# FMC_connector.net
KiCad netlist of a schematic drawn in Altium Designer
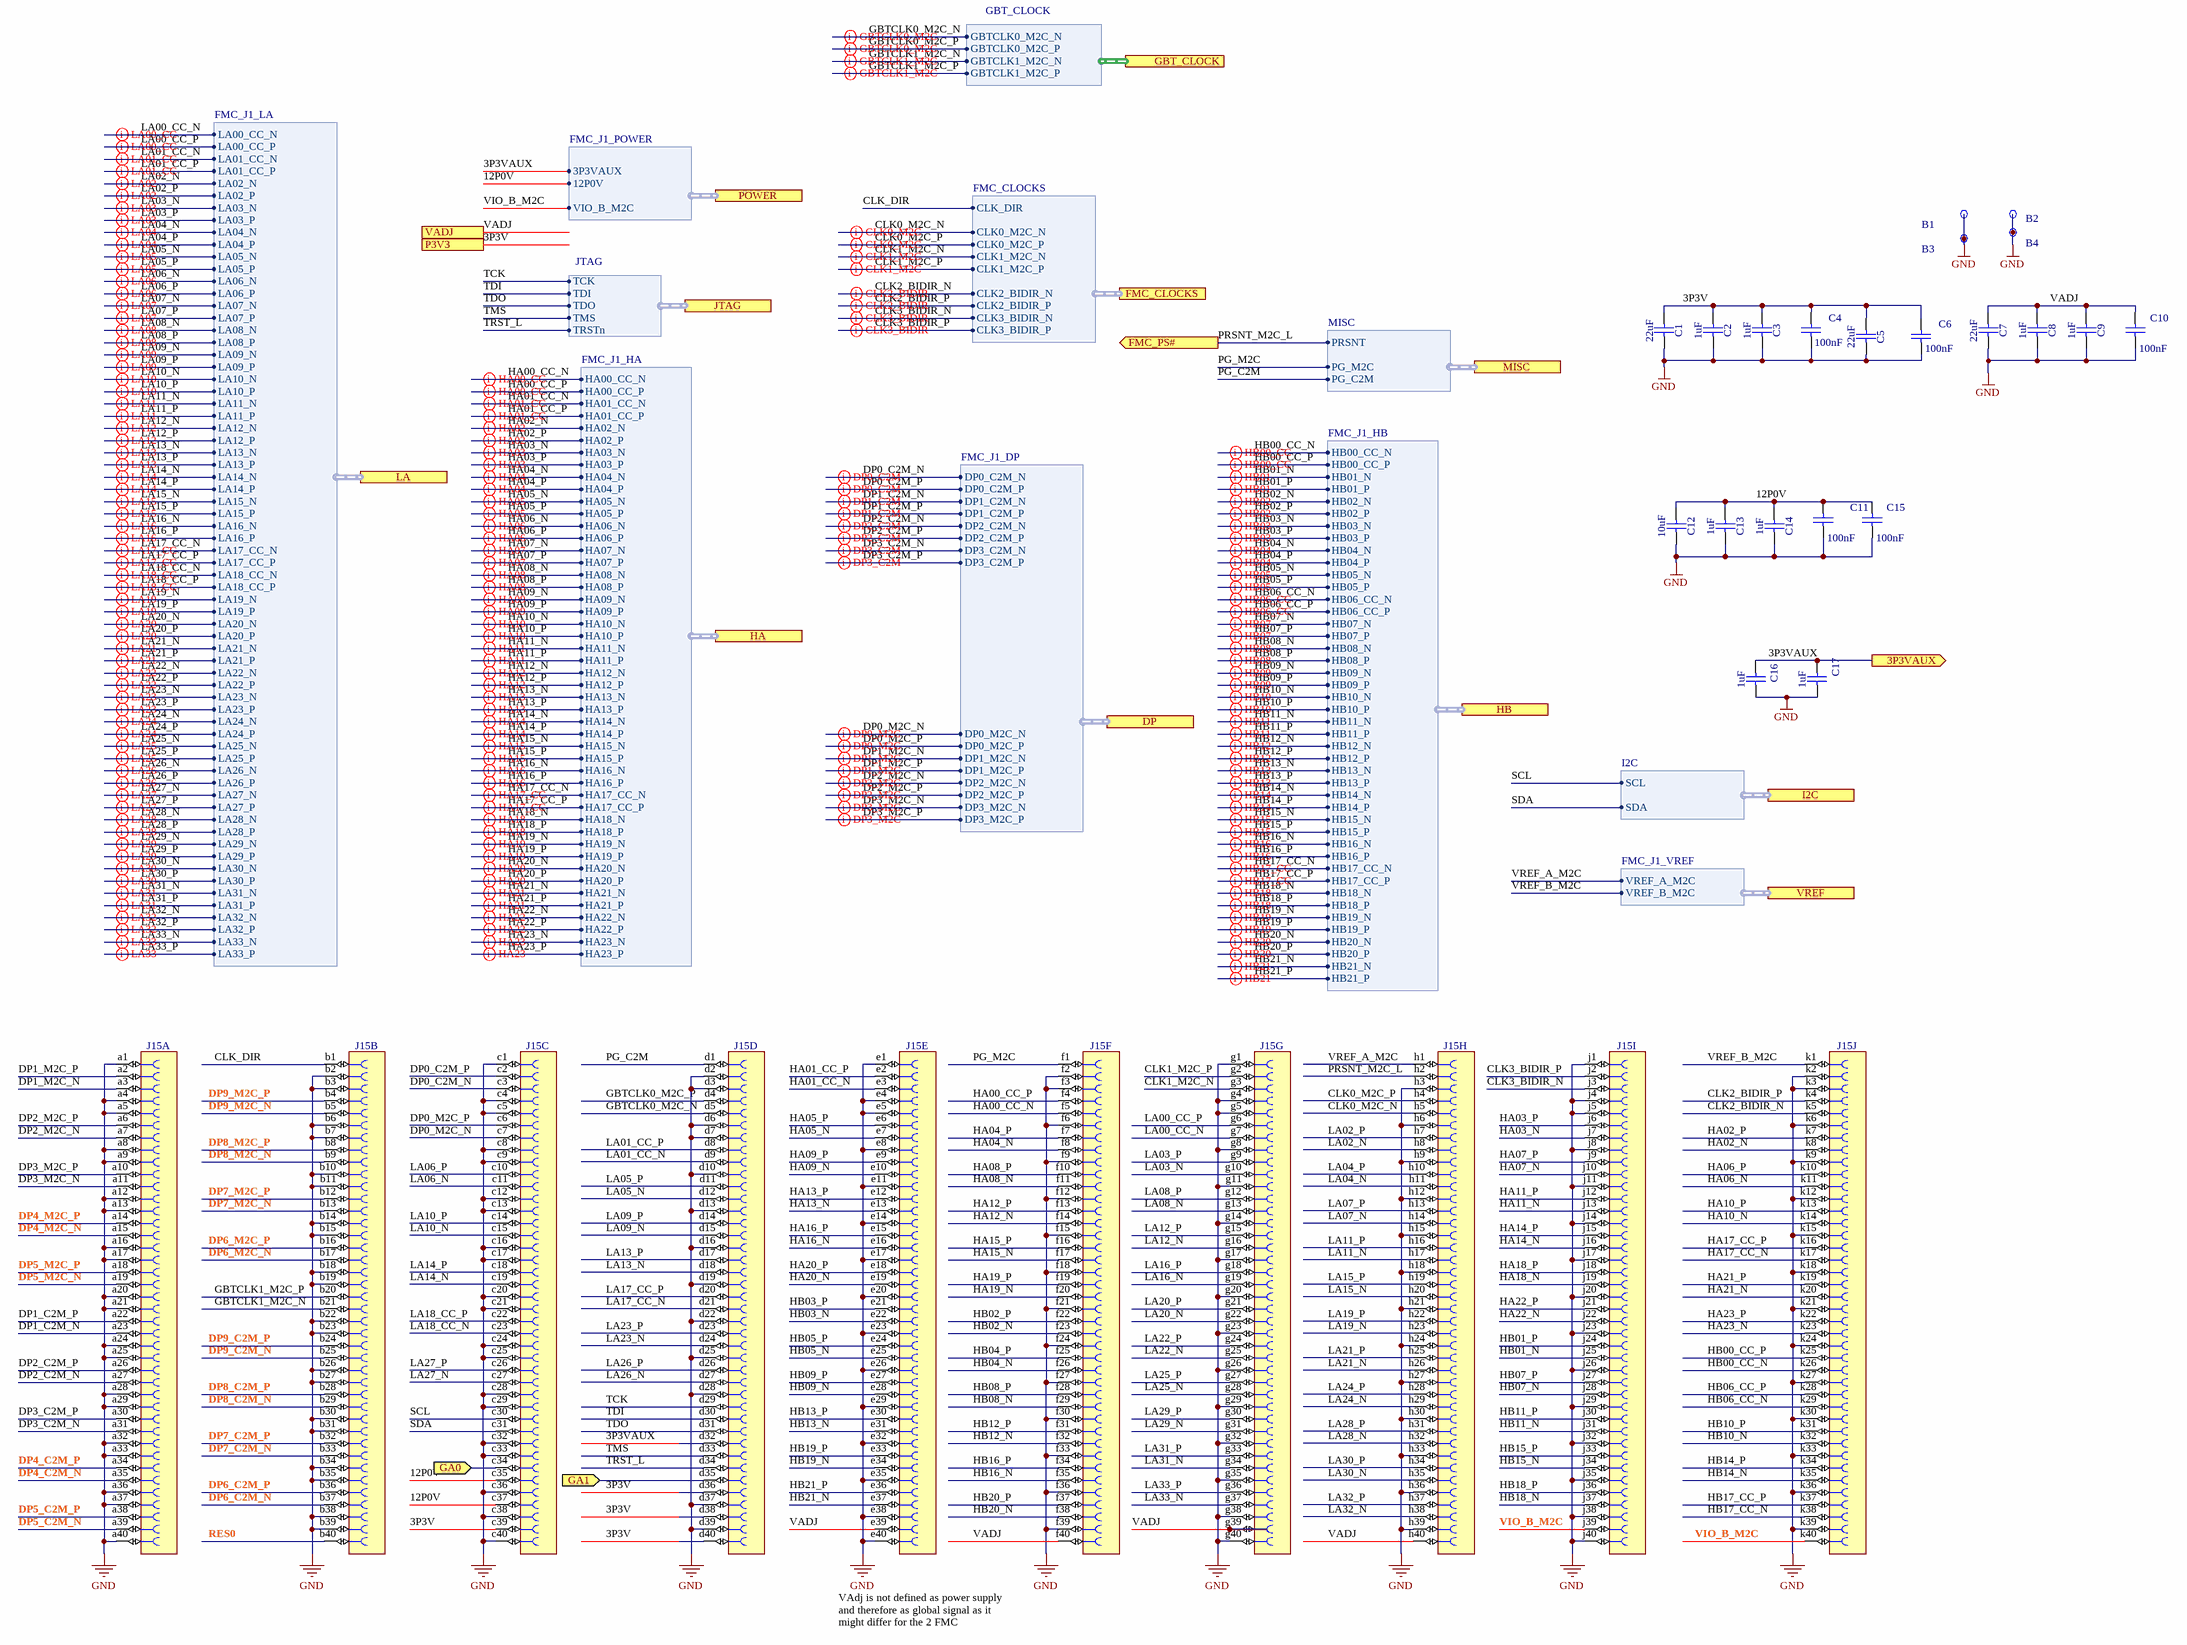
[diagram p0: FMC_connector.SchDoc]

(export (version "E")
  (design (tool "Eeschema 10.0.6"))
  (components
    (comp (ref "B1")
      (value "Plated Hole")
      (footprint "MTG270_500")
      (description "Single Terminal Socket")
      (fields (field (name "PART NUMBER") "PLATED_HOLE2.7_PAD5.0") (field (name "AUTHOR") "CERN DEM JMW"))
      (libsource (lib "Eletro-mechanical") (part "Single Terminal Socket"))
    )
    (comp (ref "B2")
      (value "Plated Hole")
      (footprint "MTG270_500")
      (description "Single Terminal Socket")
      (fields (field (name "PART NUMBER") "PLATED_HOLE2.7_PAD5.0") (field (name "AUTHOR") "CERN DEM JMW"))
      (libsource (lib "Eletro-mechanical") (part "Single Terminal Socket"))
    )
    (comp (ref "B3")
      (value "Plated Hole")
      (footprint "MTG270_500")
      (description "Single Terminal Socket")
      (fields (field (name "PART NUMBER") "PLATED_HOLE2.7_PAD5.0") (field (name "AUTHOR") "CERN DEM JMW"))
      (libsource (lib "Eletro-mechanical") (part "Single Terminal Socket"))
    )
    (comp (ref "B4")
      (value "Plated Hole")
      (footprint "MTG270_500")
      (description "Single Terminal Socket")
      (fields (field (name "PART NUMBER") "PLATED_HOLE2.7_PAD5.0") (field (name "AUTHOR") "CERN DEM JMW"))
      (libsource (lib "Eletro-mechanical") (part "Single Terminal Socket"))
    )
    (comp (ref "C1")
      (value "22uF")
      (footprint "CAPC3216X180N")
      (description "Non-polarised capacitor")
      (fields
        (field (name "PART NUMBER") "CC1206_22UF_10V_10%_X7R")
        (field (name "VOLTAGE") "10V")
        (field (name "AUTHOR") "CERN DEM JLC")
      )
      (libsource (lib "Capacitors") (part "Capacitor - non polarized"))
    )
    (comp (ref "C2")
      (value "1uF")
      (footprint "CAPC1608X87N")
      (description "Non-polarised capacitor")
      (fields
        (field (name "PART NUMBER") "CC0603_1UF_16V_10%_X7R")
        (field (name "VOLTAGE") "16V")
        (field (name "AUTHOR") "CERN DEM JLC")
      )
      (libsource (lib "Capacitors") (part "Capacitor - non polarized"))
    )
    (comp (ref "C3")
      (value "1uF")
      (footprint "CAPC1608X87N")
      (description "Non-polarised capacitor")
      (fields
        (field (name "PART NUMBER") "CC0603_1UF_16V_10%_X7R")
        (field (name "VOLTAGE") "16V")
        (field (name "AUTHOR") "CERN DEM JLC")
      )
      (libsource (lib "Capacitors") (part "Capacitor - non polarized"))
    )
    (comp (ref "C4")
      (value "100nF")
      (footprint "CAPC0603X33N")
      (description "Non-polarised capacitor")
      (fields
        (field (name "PART NUMBER") "CC0201_100NF_6.3V_10%_X5R")
        (field (name "VOLTAGE") "6.3V")
        (field (name "AUTHOR") "CERN DEM JLC")
      )
      (libsource (lib "Capacitors") (part "Capacitor - non polarized"))
    )
    (comp (ref "C5")
      (value "22uF")
      (footprint "CAPC3216X180N")
      (description "Non-polarised capacitor")
      (fields
        (field (name "PART NUMBER") "CC1206_22UF_10V_10%_X7R")
        (field (name "VOLTAGE") "10V")
        (field (name "AUTHOR") "CERN DEM JLC")
      )
      (libsource (lib "Capacitors") (part "Capacitor - non polarized"))
    )
    (comp (ref "C6")
      (value "100nF")
      (footprint "CAPC0603X33N")
      (description "Non-polarised capacitor")
      (fields
        (field (name "PART NUMBER") "CC0201_100NF_6.3V_10%_X5R")
        (field (name "VOLTAGE") "6.3V")
        (field (name "AUTHOR") "CERN DEM JLC")
      )
      (libsource (lib "Capacitors") (part "Capacitor - non polarized"))
    )
    (comp (ref "C7")
      (value "22uF")
      (footprint "CAPC3216X180N")
      (description "Non-polarised capacitor")
      (fields
        (field (name "PART NUMBER") "CC1206_22UF_10V_10%_X7R")
        (field (name "VOLTAGE") "10V")
        (field (name "AUTHOR") "CERN DEM JLC")
      )
      (libsource (lib "Capacitors") (part "Capacitor - non polarized"))
    )
    (comp (ref "C8")
      (value "1uF")
      (footprint "CAPC1608X87N")
      (description "Non-polarised capacitor")
      (fields
        (field (name "PART NUMBER") "CC0603_1UF_16V_10%_X7R")
        (field (name "VOLTAGE") "16V")
        (field (name "AUTHOR") "CERN DEM JLC")
      )
      (libsource (lib "Capacitors") (part "Capacitor - non polarized"))
    )
    (comp (ref "C9")
      (value "1uF")
      (footprint "CAPC1608X87N")
      (description "Non-polarised capacitor")
      (fields
        (field (name "PART NUMBER") "CC0603_1UF_16V_10%_X7R")
        (field (name "VOLTAGE") "16V")
        (field (name "AUTHOR") "CERN DEM JLC")
      )
      (libsource (lib "Capacitors") (part "Capacitor - non polarized"))
    )
    (comp (ref "C10")
      (value "100nF")
      (footprint "CAPC0603X33N")
      (description "Non-polarised capacitor")
      (fields
        (field (name "PART NUMBER") "CC0201_100NF_6.3V_10%_X5R")
        (field (name "VOLTAGE") "6.3V")
        (field (name "AUTHOR") "CERN DEM JLC")
      )
      (libsource (lib "Capacitors") (part "Capacitor - non polarized"))
    )
    (comp (ref "C11")
      (value "100nF")
      (footprint "CAPC0603X33N")
      (description "Non-polarised capacitor")
      (fields
        (field (name "PART NUMBER") "CC0201_100NF_6.3V_10%_X5R")
        (field (name "VOLTAGE") "6.3V")
        (field (name "AUTHOR") "CERN DEM JLC")
      )
      (libsource (lib "Capacitors") (part "Capacitor - non polarized"))
    )
    (comp (ref "C12")
      (value "10uF")
      (footprint "CAPC2012X135N")
      (description "Non-polarised capacitor")
      (fields
        (field (name "PART NUMBER") "CC0805_10UF_16V_10%_X5R")
        (field (name "VOLTAGE") "16V")
        (field (name "AUTHOR") "CERN DEM JLC")
      )
      (libsource (lib "Capacitors") (part "Capacitor - non polarized"))
    )
    (comp (ref "C13")
      (value "1uF")
      (footprint "CAPC1608X87N")
      (description "Non-polarised capacitor")
      (fields
        (field (name "PART NUMBER") "CC0603_1UF_16V_10%_X7R")
        (field (name "VOLTAGE") "16V")
        (field (name "AUTHOR") "CERN DEM JLC")
      )
      (libsource (lib "Capacitors") (part "Capacitor - non polarized"))
    )
    (comp (ref "C14")
      (value "1uF")
      (footprint "CAPC1608X87N")
      (description "Non-polarised capacitor")
      (fields
        (field (name "PART NUMBER") "CC0603_1UF_16V_10%_X7R")
        (field (name "VOLTAGE") "16V")
        (field (name "AUTHOR") "CERN DEM JLC")
      )
      (libsource (lib "Capacitors") (part "Capacitor - non polarized"))
    )
    (comp (ref "C15")
      (value "100nF")
      (footprint "CAPC0603X33N")
      (description "Non-polarised capacitor")
      (fields
        (field (name "PART NUMBER") "CC0201_100NF_6.3V_10%_X5R")
        (field (name "VOLTAGE") "6.3V")
        (field (name "AUTHOR") "CERN DEM JLC")
      )
      (libsource (lib "Capacitors") (part "Capacitor - non polarized"))
    )
    (comp (ref "C16")
      (value "1uF")
      (footprint "CAPC1608X87N")
      (description "Non-polarised capacitor")
      (fields
        (field (name "PART NUMBER") "CC0603_1UF_16V_10%_X7R")
        (field (name "VOLTAGE") "16V")
        (field (name "AUTHOR") "CERN DEM JLC")
      )
      (libsource (lib "Capacitors") (part "Capacitor - non polarized"))
    )
    (comp (ref "C17")
      (value "1uF")
      (footprint "CAPC1608X87N")
      (description "Non-polarised capacitor")
      (fields
        (field (name "PART NUMBER") "CC0603_1UF_16V_10%_X7R")
        (field (name "VOLTAGE") "16V")
        (field (name "AUTHOR") "CERN DEM JLC")
      )
      (libsource (lib "Capacitors") (part "Capacitor - non polarized"))
    )
    (comp (ref "J15")
      (value "VITA 57")
      (footprint "SAMTEC_ASP-134486-01")
      (description "Connector VITA 57, 400 Female contacts in 10 row abcdefghj")
      (fields
        (field (name "PART NUMBER") "SAMTEC_ASP-134486-01")
        (field (name "MANUFACTURER") "SAMTEC")
        (field (name "AUTHOR") "CERN DEM JLC")
      )
      (libsource (lib "Connectors") (part "Connector VITA 57 400 Female (abcdefghjk)"))
    )
  )
  (nets
    (net (code "12") (name "/3P3V") (class "Default")
      (node (ref "C1") (pin "1") (pinfunction "1_1") (pintype "passive"))
      (node (ref "C2") (pin "1") (pinfunction "1_1") (pintype "passive"))
      (node (ref "C3") (pin "1") (pinfunction "1_1") (pintype "passive"))
      (node (ref "C4") (pin "2") (pinfunction "2_2") (pintype "passive"))
      (node (ref "C5") (pin "1") (pinfunction "1_1") (pintype "passive"))
      (node (ref "C6") (pin "2") (pinfunction "2_2") (pintype "passive"))
      (node (ref "J15") (pin "c39") (pinfunction "c39_c39") (pintype "bidirectional"))
      (node (ref "J15") (pin "d36") (pinfunction "d36_d36") (pintype "bidirectional"))
      (node (ref "J15") (pin "d38") (pinfunction "d38_d38") (pintype "bidirectional"))
      (node (ref "J15") (pin "d40") (pinfunction "d40_d40") (pintype "bidirectional"))
    )
    (net (code "13") (name "/3P3VAUX") (class "Default")
      (node (ref "C16") (pin "1") (pinfunction "1_1") (pintype "passive"))
      (node (ref "C17") (pin "1") (pinfunction "1_1") (pintype "passive"))
      (node (ref "J15") (pin "d32") (pinfunction "d32_d32") (pintype "bidirectional"))
    )
    (net (code "14") (name "/12P0V") (class "Default")
      (node (ref "C11") (pin "2") (pinfunction "2_2") (pintype "passive"))
      (node (ref "C12") (pin "1") (pinfunction "1_1") (pintype "passive"))
      (node (ref "C13") (pin "1") (pinfunction "1_1") (pintype "passive"))
      (node (ref "C14") (pin "1") (pinfunction "1_1") (pintype "passive"))
      (node (ref "C15") (pin "2") (pinfunction "2_2") (pintype "passive"))
      (node (ref "J15") (pin "c35") (pinfunction "c35_c35") (pintype "bidirectional"))
      (node (ref "J15") (pin "c37") (pinfunction "c37_c37") (pintype "bidirectional"))
    )
    (net (code "15") (name "/CLK0_M2C_N") (class "Default")
      (node (ref "J15") (pin "h5") (pinfunction "h5_h5") (pintype "bidirectional"))
    )
    (net (code "16") (name "/CLK0_M2C_P") (class "Default")
      (node (ref "J15") (pin "h4") (pinfunction "h4_h4") (pintype "bidirectional"))
    )
    (net (code "17") (name "/CLK1_M2C_N") (class "Default")
      (node (ref "J15") (pin "g3") (pinfunction "g3_g3") (pintype "bidirectional"))
    )
    (net (code "18") (name "/CLK1_M2C_P") (class "Default")
      (node (ref "J15") (pin "g2") (pinfunction "g2_g2") (pintype "bidirectional"))
    )
    (net (code "19") (name "/CLK2_BIDIR_N") (class "Default")
      (node (ref "J15") (pin "k5") (pinfunction "k5_k5") (pintype "bidirectional"))
    )
    (net (code "20") (name "/CLK2_BIDIR_P") (class "Default")
      (node (ref "J15") (pin "k4") (pinfunction "k4_k4") (pintype "bidirectional"))
    )
    (net (code "21") (name "/CLK3_BIDIR_N") (class "Default")
      (node (ref "J15") (pin "j3") (pinfunction "j3_j3") (pintype "bidirectional"))
    )
    (net (code "22") (name "/CLK3_BIDIR_P") (class "Default")
      (node (ref "J15") (pin "j2") (pinfunction "j2_j2") (pintype "bidirectional"))
    )
    (net (code "23") (name "/CLK_DIR") (class "Default")
      (node (ref "J15") (pin "b1") (pinfunction "b1_b1") (pintype "bidirectional"))
    )
    (net (code "24") (name "/DP0_C2M_N") (class "Default")
      (node (ref "J15") (pin "c3") (pinfunction "c3_c3") (pintype "bidirectional"))
    )
    (net (code "25") (name "/DP0_C2M_P") (class "Default")
      (node (ref "J15") (pin "c2") (pinfunction "c2_c2") (pintype "bidirectional"))
    )
    (net (code "26") (name "/DP0_M2C_N") (class "Default")
      (node (ref "J15") (pin "c7") (pinfunction "c7_c7") (pintype "bidirectional"))
    )
    (net (code "27") (name "/DP0_M2C_P") (class "Default")
      (node (ref "J15") (pin "c6") (pinfunction "c6_c6") (pintype "bidirectional"))
    )
    (net (code "28") (name "/DP1_C2M_N") (class "Default")
      (node (ref "J15") (pin "a23") (pinfunction "a23_a23") (pintype "bidirectional"))
    )
    (net (code "29") (name "/DP1_C2M_P") (class "Default")
      (node (ref "J15") (pin "a22") (pinfunction "a22_a22") (pintype "bidirectional"))
    )
    (net (code "30") (name "/DP1_M2C_N") (class "Default")
      (node (ref "J15") (pin "a3") (pinfunction "a3_a3") (pintype "bidirectional"))
    )
    (net (code "31") (name "/DP1_M2C_P") (class "Default")
      (node (ref "J15") (pin "a2") (pinfunction "a2_a2") (pintype "bidirectional"))
    )
    (net (code "32") (name "/DP2_C2M_N") (class "Default")
      (node (ref "J15") (pin "a27") (pinfunction "a27_a27") (pintype "bidirectional"))
    )
    (net (code "33") (name "/DP2_C2M_P") (class "Default")
      (node (ref "J15") (pin "a26") (pinfunction "a26_a26") (pintype "bidirectional"))
    )
    (net (code "34") (name "/DP2_M2C_N") (class "Default")
      (node (ref "J15") (pin "a7") (pinfunction "a7_a7") (pintype "bidirectional"))
    )
    (net (code "35") (name "/DP2_M2C_P") (class "Default")
      (node (ref "J15") (pin "a6") (pinfunction "a6_a6") (pintype "bidirectional"))
    )
    (net (code "36") (name "/DP3_C2M_N") (class "Default")
      (node (ref "J15") (pin "a31") (pinfunction "a31_a31") (pintype "bidirectional"))
    )
    (net (code "37") (name "/DP3_C2M_P") (class "Default")
      (node (ref "J15") (pin "a30") (pinfunction "a30_a30") (pintype "bidirectional"))
    )
    (net (code "38") (name "/DP3_M2C_N") (class "Default")
      (node (ref "J15") (pin "a11") (pinfunction "a11_a11") (pintype "bidirectional"))
    )
    (net (code "39") (name "/DP3_M2C_P") (class "Default")
      (node (ref "J15") (pin "a10") (pinfunction "a10_a10") (pintype "bidirectional"))
    )
    (net (code "40") (name "/GA0") (class "Default")
      (node (ref "J15") (pin "c34") (pinfunction "c34_c34") (pintype "bidirectional"))
    )
    (net (code "41") (name "/GA1") (class "Default")
      (node (ref "J15") (pin "d35") (pinfunction "d35_d35") (pintype "bidirectional"))
    )
    (net (code "42") (name "/GBTCLK0_M2C_N") (class "Default")
      (node (ref "J15") (pin "d5") (pinfunction "d5_d5") (pintype "bidirectional"))
    )
    (net (code "43") (name "/GBTCLK0_M2C_P") (class "Default")
      (node (ref "J15") (pin "d4") (pinfunction "d4_d4") (pintype "bidirectional"))
    )
    (net (code "44") (name "/GBTCLK1_M2C_N") (class "Default")
      (node (ref "J15") (pin "b21") (pinfunction "b21_b21") (pintype "bidirectional"))
    )
    (net (code "45") (name "/GBTCLK1_M2C_P") (class "Default")
      (node (ref "J15") (pin "b20") (pinfunction "b20_b20") (pintype "bidirectional"))
    )
    (net (code "46") (name "/HA00_CC_N") (class "Default")
      (node (ref "J15") (pin "f5") (pinfunction "f5_f5") (pintype "bidirectional"))
    )
    (net (code "47") (name "/HA00_CC_P") (class "Default")
      (node (ref "J15") (pin "f4") (pinfunction "f4_f4") (pintype "bidirectional"))
    )
    (net (code "48") (name "/HA01_CC_N") (class "Default")
      (node (ref "J15") (pin "e3") (pinfunction "e3_e3") (pintype "bidirectional"))
    )
    (net (code "49") (name "/HA01_CC_P") (class "Default")
      (node (ref "J15") (pin "e2") (pinfunction "e2_e2") (pintype "bidirectional"))
    )
    (net (code "50") (name "/HA02_N") (class "Default")
      (node (ref "J15") (pin "k8") (pinfunction "k8_k8") (pintype "bidirectional"))
    )
    (net (code "51") (name "/HA02_P") (class "Default")
      (node (ref "J15") (pin "k7") (pinfunction "k7_k7") (pintype "bidirectional"))
    )
    (net (code "52") (name "/HA03_N") (class "Default")
      (node (ref "J15") (pin "j7") (pinfunction "j7_j7") (pintype "bidirectional"))
    )
    (net (code "53") (name "/HA03_P") (class "Default")
      (node (ref "J15") (pin "j6") (pinfunction "j6_j6") (pintype "bidirectional"))
    )
    (net (code "54") (name "/HA04_N") (class "Default")
      (node (ref "J15") (pin "f8") (pinfunction "f8_f8") (pintype "bidirectional"))
    )
    (net (code "55") (name "/HA04_P") (class "Default")
      (node (ref "J15") (pin "f7") (pinfunction "f7_f7") (pintype "bidirectional"))
    )
    (net (code "56") (name "/HA05_N") (class "Default")
      (node (ref "J15") (pin "e7") (pinfunction "e7_e7") (pintype "bidirectional"))
    )
    (net (code "57") (name "/HA05_P") (class "Default")
      (node (ref "J15") (pin "e6") (pinfunction "e6_e6") (pintype "bidirectional"))
    )
    (net (code "58") (name "/HA06_N") (class "Default")
      (node (ref "J15") (pin "k11") (pinfunction "k11_k11") (pintype "bidirectional"))
    )
    (net (code "59") (name "/HA06_P") (class "Default")
      (node (ref "J15") (pin "k10") (pinfunction "k10_k10") (pintype "bidirectional"))
    )
    (net (code "60") (name "/HA07_N") (class "Default")
      (node (ref "J15") (pin "j10") (pinfunction "j10_j10") (pintype "bidirectional"))
    )
    (net (code "61") (name "/HA07_P") (class "Default")
      (node (ref "J15") (pin "j9") (pinfunction "j9_j9") (pintype "bidirectional"))
    )
    (net (code "62") (name "/HA08_N") (class "Default")
      (node (ref "J15") (pin "f11") (pinfunction "f11_f11") (pintype "bidirectional"))
    )
    (net (code "63") (name "/HA08_P") (class "Default")
      (node (ref "J15") (pin "f10") (pinfunction "f10_f10") (pintype "bidirectional"))
    )
    (net (code "64") (name "/HA09_N") (class "Default")
      (node (ref "J15") (pin "e10") (pinfunction "e10_e10") (pintype "bidirectional"))
    )
    (net (code "65") (name "/HA09_P") (class "Default")
      (node (ref "J15") (pin "e9") (pinfunction "e9_e9") (pintype "bidirectional"))
    )
    (net (code "66") (name "/HA10_N") (class "Default")
      (node (ref "J15") (pin "k14") (pinfunction "k14_k14") (pintype "bidirectional"))
    )
    (net (code "67") (name "/HA10_P") (class "Default")
      (node (ref "J15") (pin "k13") (pinfunction "k13_k13") (pintype "bidirectional"))
    )
    (net (code "68") (name "/HA11_N") (class "Default")
      (node (ref "J15") (pin "j13") (pinfunction "j13_j13") (pintype "bidirectional"))
    )
    (net (code "69") (name "/HA11_P") (class "Default")
      (node (ref "J15") (pin "j12") (pinfunction "j12_j12") (pintype "bidirectional"))
    )
    (net (code "70") (name "/HA12_N") (class "Default")
      (node (ref "J15") (pin "f14") (pinfunction "f14_f14") (pintype "bidirectional"))
    )
    (net (code "71") (name "/HA12_P") (class "Default")
      (node (ref "J15") (pin "f13") (pinfunction "f13_f13") (pintype "bidirectional"))
    )
    (net (code "72") (name "/HA13_N") (class "Default")
      (node (ref "J15") (pin "e13") (pinfunction "e13_e13") (pintype "bidirectional"))
    )
    (net (code "73") (name "/HA13_P") (class "Default")
      (node (ref "J15") (pin "e12") (pinfunction "e12_e12") (pintype "bidirectional"))
    )
    (net (code "74") (name "/HA14_N") (class "Default")
      (node (ref "J15") (pin "j16") (pinfunction "j16_j16") (pintype "bidirectional"))
    )
    (net (code "75") (name "/HA14_P") (class "Default")
      (node (ref "J15") (pin "j15") (pinfunction "j15_j15") (pintype "bidirectional"))
    )
    (net (code "76") (name "/HA15_N") (class "Default")
      (node (ref "J15") (pin "f17") (pinfunction "f17_f17") (pintype "bidirectional"))
    )
    (net (code "77") (name "/HA15_P") (class "Default")
      (node (ref "J15") (pin "f16") (pinfunction "f16_f16") (pintype "bidirectional"))
    )
    (net (code "78") (name "/HA16_N") (class "Default")
      (node (ref "J15") (pin "e16") (pinfunction "e16_e16") (pintype "bidirectional"))
    )
    (net (code "79") (name "/HA16_P") (class "Default")
      (node (ref "J15") (pin "e15") (pinfunction "e15_e15") (pintype "bidirectional"))
    )
    (net (code "80") (name "/HA17_CC_N") (class "Default")
      (node (ref "J15") (pin "k17") (pinfunction "k17_k17") (pintype "bidirectional"))
    )
    (net (code "81") (name "/HA17_CC_P") (class "Default")
      (node (ref "J15") (pin "k16") (pinfunction "k16_k16") (pintype "bidirectional"))
    )
    (net (code "82") (name "/HA18_N") (class "Default")
      (node (ref "J15") (pin "j19") (pinfunction "j19_j19") (pintype "bidirectional"))
    )
    (net (code "83") (name "/HA18_P") (class "Default")
      (node (ref "J15") (pin "j18") (pinfunction "j18_j18") (pintype "bidirectional"))
    )
    (net (code "84") (name "/HA19_N") (class "Default")
      (node (ref "J15") (pin "f20") (pinfunction "f20_f20") (pintype "bidirectional"))
    )
    (net (code "85") (name "/HA19_P") (class "Default")
      (node (ref "J15") (pin "f19") (pinfunction "f19_f19") (pintype "bidirectional"))
    )
    (net (code "86") (name "/HA20_N") (class "Default")
      (node (ref "J15") (pin "e19") (pinfunction "e19_e19") (pintype "bidirectional"))
    )
    (net (code "87") (name "/HA20_P") (class "Default")
      (node (ref "J15") (pin "e18") (pinfunction "e18_e18") (pintype "bidirectional"))
    )
    (net (code "88") (name "/HA21_N") (class "Default")
      (node (ref "J15") (pin "k20") (pinfunction "k20_k20") (pintype "bidirectional"))
    )
    (net (code "89") (name "/HA21_P") (class "Default")
      (node (ref "J15") (pin "k19") (pinfunction "k19_k19") (pintype "bidirectional"))
    )
    (net (code "90") (name "/HA22_N") (class "Default")
      (node (ref "J15") (pin "j22") (pinfunction "j22_j22") (pintype "bidirectional"))
    )
    (net (code "91") (name "/HA22_P") (class "Default")
      (node (ref "J15") (pin "j21") (pinfunction "j21_j21") (pintype "bidirectional"))
    )
    (net (code "92") (name "/HA23_N") (class "Default")
      (node (ref "J15") (pin "k23") (pinfunction "k23_k23") (pintype "bidirectional"))
    )
    (net (code "93") (name "/HA23_P") (class "Default")
      (node (ref "J15") (pin "k22") (pinfunction "k22_k22") (pintype "bidirectional"))
    )
    (net (code "94") (name "/HB00_CC_N") (class "Default")
      (node (ref "J15") (pin "k26") (pinfunction "k26_k26") (pintype "bidirectional"))
    )
    (net (code "95") (name "/HB00_CC_P") (class "Default")
      (node (ref "J15") (pin "k25") (pinfunction "k25_k25") (pintype "bidirectional"))
    )
    (net (code "96") (name "/HB01_N") (class "Default")
      (node (ref "J15") (pin "j25") (pinfunction "j25_j25") (pintype "bidirectional"))
    )
    (net (code "97") (name "/HB01_P") (class "Default")
      (node (ref "J15") (pin "j24") (pinfunction "j24_j24") (pintype "bidirectional"))
    )
    (net (code "98") (name "/HB02_N") (class "Default")
      (node (ref "J15") (pin "f23") (pinfunction "f23_f23") (pintype "bidirectional"))
    )
    (net (code "99") (name "/HB02_P") (class "Default")
      (node (ref "J15") (pin "f22") (pinfunction "f22_f22") (pintype "bidirectional"))
    )
    (net (code "100") (name "/HB03_N") (class "Default")
      (node (ref "J15") (pin "e22") (pinfunction "e22_e22") (pintype "bidirectional"))
    )
    (net (code "101") (name "/HB03_P") (class "Default")
      (node (ref "J15") (pin "e21") (pinfunction "e21_e21") (pintype "bidirectional"))
    )
    (net (code "102") (name "/HB04_N") (class "Default")
      (node (ref "J15") (pin "f26") (pinfunction "f26_f26") (pintype "bidirectional"))
    )
    (net (code "103") (name "/HB04_P") (class "Default")
      (node (ref "J15") (pin "f25") (pinfunction "f25_f25") (pintype "bidirectional"))
    )
    (net (code "104") (name "/HB05_N") (class "Default")
      (node (ref "J15") (pin "e25") (pinfunction "e25_e25") (pintype "bidirectional"))
    )
    (net (code "105") (name "/HB05_P") (class "Default")
      (node (ref "J15") (pin "e24") (pinfunction "e24_e24") (pintype "bidirectional"))
    )
    (net (code "106") (name "/HB06_CC_N") (class "Default")
      (node (ref "J15") (pin "k29") (pinfunction "k29_k29") (pintype "bidirectional"))
    )
    (net (code "107") (name "/HB06_CC_P") (class "Default")
      (node (ref "J15") (pin "k28") (pinfunction "k28_k28") (pintype "bidirectional"))
    )
    (net (code "108") (name "/HB07_N") (class "Default")
      (node (ref "J15") (pin "j28") (pinfunction "j28_j28") (pintype "bidirectional"))
    )
    (net (code "109") (name "/HB07_P") (class "Default")
      (node (ref "J15") (pin "j27") (pinfunction "j27_j27") (pintype "bidirectional"))
    )
    (net (code "110") (name "/HB08_N") (class "Default")
      (node (ref "J15") (pin "f29") (pinfunction "f29_f29") (pintype "bidirectional"))
    )
    (net (code "111") (name "/HB08_P") (class "Default")
      (node (ref "J15") (pin "f28") (pinfunction "f28_f28") (pintype "bidirectional"))
    )
    (net (code "112") (name "/HB09_N") (class "Default")
      (node (ref "J15") (pin "e28") (pinfunction "e28_e28") (pintype "bidirectional"))
    )
    (net (code "113") (name "/HB09_P") (class "Default")
      (node (ref "J15") (pin "e27") (pinfunction "e27_e27") (pintype "bidirectional"))
    )
    (net (code "114") (name "/HB10_N") (class "Default")
      (node (ref "J15") (pin "k32") (pinfunction "k32_k32") (pintype "bidirectional"))
    )
    (net (code "115") (name "/HB10_P") (class "Default")
      (node (ref "J15") (pin "k31") (pinfunction "k31_k31") (pintype "bidirectional"))
    )
    (net (code "116") (name "/HB11_N") (class "Default")
      (node (ref "J15") (pin "j31") (pinfunction "j31_j31") (pintype "bidirectional"))
    )
    (net (code "117") (name "/HB11_P") (class "Default")
      (node (ref "J15") (pin "j30") (pinfunction "j30_j30") (pintype "bidirectional"))
    )
    (net (code "118") (name "/HB12_N") (class "Default")
      (node (ref "J15") (pin "f32") (pinfunction "f32_f32") (pintype "bidirectional"))
    )
    (net (code "119") (name "/HB12_P") (class "Default")
      (node (ref "J15") (pin "f31") (pinfunction "f31_f31") (pintype "bidirectional"))
    )
    (net (code "120") (name "/HB13_N") (class "Default")
      (node (ref "J15") (pin "e31") (pinfunction "e31_e31") (pintype "bidirectional"))
    )
    (net (code "121") (name "/HB13_P") (class "Default")
      (node (ref "J15") (pin "e30") (pinfunction "e30_e30") (pintype "bidirectional"))
    )
    (net (code "122") (name "/HB14_N") (class "Default")
      (node (ref "J15") (pin "k35") (pinfunction "k35_k35") (pintype "bidirectional"))
    )
    (net (code "123") (name "/HB14_P") (class "Default")
      (node (ref "J15") (pin "k34") (pinfunction "k34_k34") (pintype "bidirectional"))
    )
    (net (code "124") (name "/HB15_N") (class "Default")
      (node (ref "J15") (pin "j34") (pinfunction "j34_j34") (pintype "bidirectional"))
    )
    (net (code "125") (name "/HB15_P") (class "Default")
      (node (ref "J15") (pin "j33") (pinfunction "j33_j33") (pintype "bidirectional"))
    )
    (net (code "126") (name "/HB16_N") (class "Default")
      (node (ref "J15") (pin "f35") (pinfunction "f35_f35") (pintype "bidirectional"))
    )
    (net (code "127") (name "/HB16_P") (class "Default")
      (node (ref "J15") (pin "f34") (pinfunction "f34_f34") (pintype "bidirectional"))
    )
    (net (code "128") (name "/HB17_CC_N") (class "Default")
      (node (ref "J15") (pin "k38") (pinfunction "k38_k38") (pintype "bidirectional"))
    )
    (net (code "129") (name "/HB17_CC_P") (class "Default")
      (node (ref "J15") (pin "k37") (pinfunction "k37_k37") (pintype "bidirectional"))
    )
    (net (code "130") (name "/HB18_N") (class "Default")
      (node (ref "J15") (pin "j37") (pinfunction "j37_j37") (pintype "bidirectional"))
    )
    (net (code "131") (name "/HB18_P") (class "Default")
      (node (ref "J15") (pin "j36") (pinfunction "j36_j36") (pintype "bidirectional"))
    )
    (net (code "132") (name "/HB19_N") (class "Default")
      (node (ref "J15") (pin "e34") (pinfunction "e34_e34") (pintype "bidirectional"))
    )
    (net (code "133") (name "/HB19_P") (class "Default")
      (node (ref "J15") (pin "e33") (pinfunction "e33_e33") (pintype "bidirectional"))
    )
    (net (code "134") (name "/HB20_N") (class "Default")
      (node (ref "J15") (pin "f38") (pinfunction "f38_f38") (pintype "bidirectional"))
    )
    (net (code "135") (name "/HB20_P") (class "Default")
      (node (ref "J15") (pin "f37") (pinfunction "f37_f37") (pintype "bidirectional"))
    )
    (net (code "136") (name "/HB21_N") (class "Default")
      (node (ref "J15") (pin "e37") (pinfunction "e37_e37") (pintype "bidirectional"))
    )
    (net (code "137") (name "/HB21_P") (class "Default")
      (node (ref "J15") (pin "e36") (pinfunction "e36_e36") (pintype "bidirectional"))
    )
    (net (code "138") (name "/LA00_CC_N") (class "Default")
      (node (ref "J15") (pin "g7") (pinfunction "g7_g7") (pintype "bidirectional"))
    )
    (net (code "139") (name "/LA00_CC_P") (class "Default")
      (node (ref "J15") (pin "g6") (pinfunction "g6_g6") (pintype "bidirectional"))
    )
    (net (code "140") (name "/LA01_CC_N") (class "Default")
      (node (ref "J15") (pin "d9") (pinfunction "d9_d9") (pintype "bidirectional"))
    )
    (net (code "141") (name "/LA01_CC_P") (class "Default")
      (node (ref "J15") (pin "d8") (pinfunction "d8_d8") (pintype "bidirectional"))
    )
    (net (code "142") (name "/LA02_N") (class "Default")
      (node (ref "J15") (pin "h8") (pinfunction "h8_h8") (pintype "bidirectional"))
    )
    (net (code "143") (name "/LA02_P") (class "Default")
      (node (ref "J15") (pin "h7") (pinfunction "h7_h7") (pintype "bidirectional"))
    )
    (net (code "144") (name "/LA03_N") (class "Default")
      (node (ref "J15") (pin "g10") (pinfunction "g10_g10") (pintype "bidirectional"))
    )
    (net (code "145") (name "/LA03_P") (class "Default")
      (node (ref "J15") (pin "g9") (pinfunction "g9_g9") (pintype "bidirectional"))
    )
    (net (code "146") (name "/LA04_N") (class "Default")
      (node (ref "J15") (pin "h11") (pinfunction "h11_h11") (pintype "bidirectional"))
    )
    (net (code "147") (name "/LA04_P") (class "Default")
      (node (ref "J15") (pin "h10") (pinfunction "h10_h10") (pintype "bidirectional"))
    )
    (net (code "148") (name "/LA05_N") (class "Default")
      (node (ref "J15") (pin "d12") (pinfunction "d12_d12") (pintype "bidirectional"))
    )
    (net (code "149") (name "/LA05_P") (class "Default")
      (node (ref "J15") (pin "d11") (pinfunction "d11_d11") (pintype "bidirectional"))
    )
    (net (code "150") (name "/LA06_N") (class "Default")
      (node (ref "J15") (pin "c11") (pinfunction "c11_c11") (pintype "bidirectional"))
    )
    (net (code "151") (name "/LA06_P") (class "Default")
      (node (ref "J15") (pin "c10") (pinfunction "c10_c10") (pintype "bidirectional"))
    )
    (net (code "152") (name "/LA07_N") (class "Default")
      (node (ref "J15") (pin "h14") (pinfunction "h14_h14") (pintype "bidirectional"))
    )
    (net (code "153") (name "/LA07_P") (class "Default")
      (node (ref "J15") (pin "h13") (pinfunction "h13_h13") (pintype "bidirectional"))
    )
    (net (code "154") (name "/LA08_N") (class "Default")
      (node (ref "J15") (pin "g13") (pinfunction "g13_g13") (pintype "bidirectional"))
    )
    (net (code "155") (name "/LA08_P") (class "Default")
      (node (ref "J15") (pin "g12") (pinfunction "g12_g12") (pintype "bidirectional"))
    )
    (net (code "156") (name "/LA09_N") (class "Default")
      (node (ref "J15") (pin "d15") (pinfunction "d15_d15") (pintype "bidirectional"))
    )
    (net (code "157") (name "/LA09_P") (class "Default")
      (node (ref "J15") (pin "d14") (pinfunction "d14_d14") (pintype "bidirectional"))
    )
    (net (code "158") (name "/LA10_N") (class "Default")
      (node (ref "J15") (pin "c15") (pinfunction "c15_c15") (pintype "bidirectional"))
    )
    (net (code "159") (name "/LA10_P") (class "Default")
      (node (ref "J15") (pin "c14") (pinfunction "c14_c14") (pintype "bidirectional"))
    )
    (net (code "160") (name "/LA11_N") (class "Default")
      (node (ref "J15") (pin "h17") (pinfunction "h17_h17") (pintype "bidirectional"))
    )
    (net (code "161") (name "/LA11_P") (class "Default")
      (node (ref "J15") (pin "h16") (pinfunction "h16_h16") (pintype "bidirectional"))
    )
    (net (code "162") (name "/LA12_N") (class "Default")
      (node (ref "J15") (pin "g16") (pinfunction "g16_g16") (pintype "bidirectional"))
    )
    (net (code "163") (name "/LA12_P") (class "Default")
      (node (ref "J15") (pin "g15") (pinfunction "g15_g15") (pintype "bidirectional"))
    )
    (net (code "164") (name "/LA13_N") (class "Default")
      (node (ref "J15") (pin "d18") (pinfunction "d18_d18") (pintype "bidirectional"))
    )
    (net (code "165") (name "/LA13_P") (class "Default")
      (node (ref "J15") (pin "d17") (pinfunction "d17_d17") (pintype "bidirectional"))
    )
    (net (code "166") (name "/LA14_N") (class "Default")
      (node (ref "J15") (pin "c19") (pinfunction "c19_c19") (pintype "bidirectional"))
    )
    (net (code "167") (name "/LA14_P") (class "Default")
      (node (ref "J15") (pin "c18") (pinfunction "c18_c18") (pintype "bidirectional"))
    )
    (net (code "168") (name "/LA15_N") (class "Default")
      (node (ref "J15") (pin "h20") (pinfunction "h20_h20") (pintype "bidirectional"))
    )
    (net (code "169") (name "/LA15_P") (class "Default")
      (node (ref "J15") (pin "h19") (pinfunction "h19_h19") (pintype "bidirectional"))
    )
    (net (code "170") (name "/LA16_N") (class "Default")
      (node (ref "J15") (pin "g19") (pinfunction "g19_g19") (pintype "bidirectional"))
    )
    (net (code "171") (name "/LA16_P") (class "Default")
      (node (ref "J15") (pin "g18") (pinfunction "g18_g18") (pintype "bidirectional"))
    )
    (net (code "172") (name "/LA17_CC_N") (class "Default")
      (node (ref "J15") (pin "d21") (pinfunction "d21_d21") (pintype "bidirectional"))
    )
    (net (code "173") (name "/LA17_CC_P") (class "Default")
      (node (ref "J15") (pin "d20") (pinfunction "d20_d20") (pintype "bidirectional"))
    )
    (net (code "174") (name "/LA18_CC_N") (class "Default")
      (node (ref "J15") (pin "c23") (pinfunction "c23_c23") (pintype "bidirectional"))
    )
    (net (code "175") (name "/LA18_CC_P") (class "Default")
      (node (ref "J15") (pin "c22") (pinfunction "c22_c22") (pintype "bidirectional"))
    )
    (net (code "176") (name "/LA19_N") (class "Default")
      (node (ref "J15") (pin "h23") (pinfunction "h23_h23") (pintype "bidirectional"))
    )
    (net (code "177") (name "/LA19_P") (class "Default")
      (node (ref "J15") (pin "h22") (pinfunction "h22_h22") (pintype "bidirectional"))
    )
    (net (code "178") (name "/LA20_N") (class "Default")
      (node (ref "J15") (pin "g22") (pinfunction "g22_g22") (pintype "bidirectional"))
    )
    (net (code "179") (name "/LA20_P") (class "Default")
      (node (ref "J15") (pin "g21") (pinfunction "g21_g21") (pintype "bidirectional"))
    )
    (net (code "180") (name "/LA21_N") (class "Default")
      (node (ref "J15") (pin "h26") (pinfunction "h26_h26") (pintype "bidirectional"))
    )
    (net (code "181") (name "/LA21_P") (class "Default")
      (node (ref "J15") (pin "h25") (pinfunction "h25_h25") (pintype "bidirectional"))
    )
    (net (code "182") (name "/LA22_N") (class "Default")
      (node (ref "J15") (pin "g25") (pinfunction "g25_g25") (pintype "bidirectional"))
    )
    (net (code "183") (name "/LA22_P") (class "Default")
      (node (ref "J15") (pin "g24") (pinfunction "g24_g24") (pintype "bidirectional"))
    )
    (net (code "184") (name "/LA23_N") (class "Default")
      (node (ref "J15") (pin "d24") (pinfunction "d24_d24") (pintype "bidirectional"))
    )
    (net (code "185") (name "/LA23_P") (class "Default")
      (node (ref "J15") (pin "d23") (pinfunction "d23_d23") (pintype "bidirectional"))
    )
    (net (code "186") (name "/LA24_N") (class "Default")
      (node (ref "J15") (pin "h29") (pinfunction "h29_h29") (pintype "bidirectional"))
    )
    (net (code "187") (name "/LA24_P") (class "Default")
      (node (ref "J15") (pin "h28") (pinfunction "h28_h28") (pintype "bidirectional"))
    )
    (net (code "188") (name "/LA25_N") (class "Default")
      (node (ref "J15") (pin "g28") (pinfunction "g28_g28") (pintype "bidirectional"))
    )
    (net (code "189") (name "/LA25_P") (class "Default")
      (node (ref "J15") (pin "g27") (pinfunction "g27_g27") (pintype "bidirectional"))
    )
    (net (code "190") (name "/LA26_N") (class "Default")
      (node (ref "J15") (pin "d27") (pinfunction "d27_d27") (pintype "bidirectional"))
    )
    (net (code "191") (name "/LA26_P") (class "Default")
      (node (ref "J15") (pin "d26") (pinfunction "d26_d26") (pintype "bidirectional"))
    )
    (net (code "192") (name "/LA27_N") (class "Default")
      (node (ref "J15") (pin "c27") (pinfunction "c27_c27") (pintype "bidirectional"))
    )
    (net (code "193") (name "/LA27_P") (class "Default")
      (node (ref "J15") (pin "c26") (pinfunction "c26_c26") (pintype "bidirectional"))
    )
    (net (code "194") (name "/LA28_N") (class "Default")
      (node (ref "J15") (pin "h32") (pinfunction "h32_h32") (pintype "bidirectional"))
    )
    (net (code "195") (name "/LA28_P") (class "Default")
      (node (ref "J15") (pin "h31") (pinfunction "h31_h31") (pintype "bidirectional"))
    )
    (net (code "196") (name "/LA29_N") (class "Default")
      (node (ref "J15") (pin "g31") (pinfunction "g31_g31") (pintype "bidirectional"))
    )
    (net (code "197") (name "/LA29_P") (class "Default")
      (node (ref "J15") (pin "g30") (pinfunction "g30_g30") (pintype "bidirectional"))
    )
    (net (code "198") (name "/LA30_N") (class "Default")
      (node (ref "J15") (pin "h35") (pinfunction "h35_h35") (pintype "bidirectional"))
    )
    (net (code "199") (name "/LA30_P") (class "Default")
      (node (ref "J15") (pin "h34") (pinfunction "h34_h34") (pintype "bidirectional"))
    )
    (net (code "200") (name "/LA31_N") (class "Default")
      (node (ref "J15") (pin "g34") (pinfunction "g34_g34") (pintype "bidirectional"))
    )
    (net (code "201") (name "/LA31_P") (class "Default")
      (node (ref "J15") (pin "g33") (pinfunction "g33_g33") (pintype "bidirectional"))
    )
    (net (code "202") (name "/LA32_N") (class "Default")
      (node (ref "J15") (pin "h38") (pinfunction "h38_h38") (pintype "bidirectional"))
    )
    (net (code "203") (name "/LA32_P") (class "Default")
      (node (ref "J15") (pin "h37") (pinfunction "h37_h37") (pintype "bidirectional"))
    )
    (net (code "204") (name "/LA33_N") (class "Default")
      (node (ref "J15") (pin "g37") (pinfunction "g37_g37") (pintype "bidirectional"))
    )
    (net (code "205") (name "/LA33_P") (class "Default")
      (node (ref "J15") (pin "g36") (pinfunction "g36_g36") (pintype "bidirectional"))
    )
    (net (code "206") (name "/PG_C2M") (class "Default")
      (node (ref "J15") (pin "d1") (pinfunction "d1_d1") (pintype "bidirectional"))
    )
    (net (code "207") (name "/PG_M2C") (class "Default")
      (node (ref "J15") (pin "f1") (pinfunction "f1_f1") (pintype "bidirectional"))
    )
    (net (code "208") (name "/PRSNT_M2C_L") (class "Default")
      (node (ref "J15") (pin "h2") (pinfunction "h2_h2") (pintype "bidirectional"))
    )
    (net (code "209") (name "/SCL") (class "Default")
      (node (ref "J15") (pin "c30") (pinfunction "c30_c30") (pintype "bidirectional"))
    )
    (net (code "210") (name "/SDA") (class "Default")
      (node (ref "J15") (pin "c31") (pinfunction "c31_c31") (pintype "bidirectional"))
    )
    (net (code "211") (name "/TCK") (class "Default")
      (node (ref "J15") (pin "d29") (pinfunction "d29_d29") (pintype "bidirectional"))
    )
    (net (code "212") (name "/TDI") (class "Default")
      (node (ref "J15") (pin "d30") (pinfunction "d30_d30") (pintype "bidirectional"))
    )
    (net (code "213") (name "/TDO") (class "Default")
      (node (ref "J15") (pin "d31") (pinfunction "d31_d31") (pintype "bidirectional"))
    )
    (net (code "214") (name "/TMS") (class "Default")
      (node (ref "J15") (pin "d33") (pinfunction "d33_d33") (pintype "bidirectional"))
    )
    (net (code "215") (name "/TRST_L") (class "Default")
      (node (ref "J15") (pin "d34") (pinfunction "d34_d34") (pintype "bidirectional"))
    )
    (net (code "216") (name "/VADJ") (class "Default")
      (node (ref "C10") (pin "2") (pinfunction "2_2") (pintype "passive"))
      (node (ref "C7") (pin "1") (pinfunction "1_1") (pintype "passive"))
      (node (ref "C8") (pin "1") (pinfunction "1_1") (pintype "passive"))
      (node (ref "C9") (pin "1") (pinfunction "1_1") (pintype "passive"))
      (node (ref "J15") (pin "e39") (pinfunction "e39_e39") (pintype "bidirectional"))
      (node (ref "J15") (pin "f40") (pinfunction "f40_f40") (pintype "bidirectional"))
      (node (ref "J15") (pin "g39") (pinfunction "g39_g39") (pintype "bidirectional"))
      (node (ref "J15") (pin "h40") (pinfunction "h40_h40") (pintype "bidirectional"))
    )
    (net (code "218") (name "/VREF_A_M2C") (class "Default")
      (node (ref "J15") (pin "h1") (pinfunction "h1_h1") (pintype "bidirectional"))
    )
    (net (code "219") (name "/VREF_B_M2C") (class "Default")
      (node (ref "J15") (pin "k1") (pinfunction "k1_k1") (pintype "bidirectional"))
    )
    (net (code "231") (name "GND") (class "Default")
      (node (ref "B1") (pin "1") (pinfunction "1_1") (pintype "bidirectional"))
      (node (ref "B2") (pin "1") (pinfunction "1_1") (pintype "bidirectional"))
      (node (ref "B3") (pin "1") (pinfunction "1_1") (pintype "bidirectional"))
      (node (ref "B4") (pin "1") (pinfunction "1_1") (pintype "bidirectional"))
      (node (ref "C1") (pin "2") (pinfunction "2_2") (pintype "passive"))
      (node (ref "C10") (pin "1") (pinfunction "1_1") (pintype "passive"))
      (node (ref "C11") (pin "1") (pinfunction "1_1") (pintype "passive"))
      (node (ref "C12") (pin "2") (pinfunction "2_2") (pintype "passive"))
      (node (ref "C13") (pin "2") (pinfunction "2_2") (pintype "passive"))
      (node (ref "C14") (pin "2") (pinfunction "2_2") (pintype "passive"))
      (node (ref "C15") (pin "1") (pinfunction "1_1") (pintype "passive"))
      (node (ref "C16") (pin "2") (pinfunction "2_2") (pintype "passive"))
      (node (ref "C17") (pin "2") (pinfunction "2_2") (pintype "passive"))
      (node (ref "C2") (pin "2") (pinfunction "2_2") (pintype "passive"))
      (node (ref "C3") (pin "2") (pinfunction "2_2") (pintype "passive"))
      (node (ref "C4") (pin "1") (pinfunction "1_1") (pintype "passive"))
      (node (ref "C5") (pin "2") (pinfunction "2_2") (pintype "passive"))
      (node (ref "C6") (pin "1") (pinfunction "1_1") (pintype "passive"))
      (node (ref "C7") (pin "2") (pinfunction "2_2") (pintype "passive"))
      (node (ref "C8") (pin "2") (pinfunction "2_2") (pintype "passive"))
      (node (ref "C9") (pin "2") (pinfunction "2_2") (pintype "passive"))
      (node (ref "J15") (pin "a1") (pinfunction "a1_a1") (pintype "bidirectional"))
      (node (ref "J15") (pin "a12") (pinfunction "a12_a12") (pintype "bidirectional"))
      (node (ref "J15") (pin "a13") (pinfunction "a13_a13") (pintype "bidirectional"))
      (node (ref "J15") (pin "a16") (pinfunction "a16_a16") (pintype "bidirectional"))
      (node (ref "J15") (pin "a17") (pinfunction "a17_a17") (pintype "bidirectional"))
      (node (ref "J15") (pin "a20") (pinfunction "a20_a20") (pintype "bidirectional"))
      (node (ref "J15") (pin "a21") (pinfunction "a21_a21") (pintype "bidirectional"))
      (node (ref "J15") (pin "a24") (pinfunction "a24_a24") (pintype "bidirectional"))
      (node (ref "J15") (pin "a25") (pinfunction "a25_a25") (pintype "bidirectional"))
      (node (ref "J15") (pin "a28") (pinfunction "a28_a28") (pintype "bidirectional"))
      (node (ref "J15") (pin "a29") (pinfunction "a29_a29") (pintype "bidirectional"))
      (node (ref "J15") (pin "a32") (pinfunction "a32_a32") (pintype "bidirectional"))
      (node (ref "J15") (pin "a33") (pinfunction "a33_a33") (pintype "bidirectional"))
      (node (ref "J15") (pin "a36") (pinfunction "a36_a36") (pintype "bidirectional"))
      (node (ref "J15") (pin "a37") (pinfunction "a37_a37") (pintype "bidirectional"))
      (node (ref "J15") (pin "a4") (pinfunction "a4_a4") (pintype "bidirectional"))
      (node (ref "J15") (pin "a40") (pinfunction "a40_a40") (pintype "bidirectional"))
      (node (ref "J15") (pin "a5") (pinfunction "a5_a5") (pintype "bidirectional"))
      (node (ref "J15") (pin "a8") (pinfunction "a8_a8") (pintype "bidirectional"))
      (node (ref "J15") (pin "a9") (pinfunction "a9_a9") (pintype "bidirectional"))
      (node (ref "J15") (pin "b10") (pinfunction "b10_b10") (pintype "bidirectional"))
      (node (ref "J15") (pin "b11") (pinfunction "b11_b11") (pintype "bidirectional"))
      (node (ref "J15") (pin "b14") (pinfunction "b14_b14") (pintype "bidirectional"))
      (node (ref "J15") (pin "b15") (pinfunction "b15_b15") (pintype "bidirectional"))
      (node (ref "J15") (pin "b18") (pinfunction "b18_b18") (pintype "bidirectional"))
      (node (ref "J15") (pin "b19") (pinfunction "b19_b19") (pintype "bidirectional"))
      (node (ref "J15") (pin "b2") (pinfunction "b2_b2") (pintype "bidirectional"))
      (node (ref "J15") (pin "b22") (pinfunction "b22_b22") (pintype "bidirectional"))
      (node (ref "J15") (pin "b23") (pinfunction "b23_b23") (pintype "bidirectional"))
      (node (ref "J15") (pin "b26") (pinfunction "b26_b26") (pintype "bidirectional"))
      (node (ref "J15") (pin "b27") (pinfunction "b27_b27") (pintype "bidirectional"))
      (node (ref "J15") (pin "b3") (pinfunction "b3_b3") (pintype "bidirectional"))
      (node (ref "J15") (pin "b30") (pinfunction "b30_b30") (pintype "bidirectional"))
      (node (ref "J15") (pin "b31") (pinfunction "b31_b31") (pintype "bidirectional"))
      (node (ref "J15") (pin "b34") (pinfunction "b34_b34") (pintype "bidirectional"))
      (node (ref "J15") (pin "b35") (pinfunction "b35_b35") (pintype "bidirectional"))
      (node (ref "J15") (pin "b38") (pinfunction "b38_b38") (pintype "bidirectional"))
      (node (ref "J15") (pin "b39") (pinfunction "b39_b39") (pintype "bidirectional"))
      (node (ref "J15") (pin "b6") (pinfunction "b6_b6") (pintype "bidirectional"))
      (node (ref "J15") (pin "b7") (pinfunction "b7_b7") (pintype "bidirectional"))
      (node (ref "J15") (pin "c1") (pinfunction "c1_c1") (pintype "bidirectional"))
      (node (ref "J15") (pin "c12") (pinfunction "c12_c12") (pintype "bidirectional"))
      (node (ref "J15") (pin "c13") (pinfunction "c13_c13") (pintype "bidirectional"))
      (node (ref "J15") (pin "c16") (pinfunction "c16_c16") (pintype "bidirectional"))
      (node (ref "J15") (pin "c17") (pinfunction "c17_c17") (pintype "bidirectional"))
      (node (ref "J15") (pin "c20") (pinfunction "c20_c20") (pintype "bidirectional"))
      (node (ref "J15") (pin "c21") (pinfunction "c21_c21") (pintype "bidirectional"))
      (node (ref "J15") (pin "c24") (pinfunction "c24_c24") (pintype "bidirectional"))
      (node (ref "J15") (pin "c25") (pinfunction "c25_c25") (pintype "bidirectional"))
      (node (ref "J15") (pin "c28") (pinfunction "c28_c28") (pintype "bidirectional"))
      (node (ref "J15") (pin "c29") (pinfunction "c29_c29") (pintype "bidirectional"))
      (node (ref "J15") (pin "c32") (pinfunction "c32_c32") (pintype "bidirectional"))
      (node (ref "J15") (pin "c33") (pinfunction "c33_c33") (pintype "bidirectional"))
      (node (ref "J15") (pin "c36") (pinfunction "c36_c36") (pintype "bidirectional"))
      (node (ref "J15") (pin "c38") (pinfunction "c38_c38") (pintype "bidirectional"))
      (node (ref "J15") (pin "c4") (pinfunction "c4_c4") (pintype "bidirectional"))
      (node (ref "J15") (pin "c40") (pinfunction "c40_c40") (pintype "bidirectional"))
      (node (ref "J15") (pin "c5") (pinfunction "c5_c5") (pintype "bidirectional"))
      (node (ref "J15") (pin "c8") (pinfunction "c8_c8") (pintype "bidirectional"))
      (node (ref "J15") (pin "c9") (pinfunction "c9_c9") (pintype "bidirectional"))
      (node (ref "J15") (pin "d10") (pinfunction "d10_d10") (pintype "bidirectional"))
      (node (ref "J15") (pin "d13") (pinfunction "d13_d13") (pintype "bidirectional"))
      (node (ref "J15") (pin "d16") (pinfunction "d16_d16") (pintype "bidirectional"))
      (node (ref "J15") (pin "d19") (pinfunction "d19_d19") (pintype "bidirectional"))
      (node (ref "J15") (pin "d2") (pinfunction "d2_d2") (pintype "bidirectional"))
      (node (ref "J15") (pin "d22") (pinfunction "d22_d22") (pintype "bidirectional"))
      (node (ref "J15") (pin "d25") (pinfunction "d25_d25") (pintype "bidirectional"))
      (node (ref "J15") (pin "d28") (pinfunction "d28_d28") (pintype "bidirectional"))
      (node (ref "J15") (pin "d3") (pinfunction "d3_d3") (pintype "bidirectional"))
      (node (ref "J15") (pin "d37") (pinfunction "d37_d37") (pintype "bidirectional"))
      (node (ref "J15") (pin "d39") (pinfunction "d39_d39") (pintype "bidirectional"))
      (node (ref "J15") (pin "d6") (pinfunction "d6_d6") (pintype "bidirectional"))
      (node (ref "J15") (pin "d7") (pinfunction "d7_d7") (pintype "bidirectional"))
      (node (ref "J15") (pin "e1") (pinfunction "e1_e1") (pintype "bidirectional"))
      (node (ref "J15") (pin "e11") (pinfunction "e11_e11") (pintype "bidirectional"))
      (node (ref "J15") (pin "e14") (pinfunction "e14_e14") (pintype "bidirectional"))
      (node (ref "J15") (pin "e17") (pinfunction "e17_e17") (pintype "bidirectional"))
      (node (ref "J15") (pin "e20") (pinfunction "e20_e20") (pintype "bidirectional"))
      (node (ref "J15") (pin "e23") (pinfunction "e23_e23") (pintype "bidirectional"))
      (node (ref "J15") (pin "e26") (pinfunction "e26_e26") (pintype "bidirectional"))
      (node (ref "J15") (pin "e29") (pinfunction "e29_e29") (pintype "bidirectional"))
      (node (ref "J15") (pin "e32") (pinfunction "e32_e32") (pintype "bidirectional"))
      (node (ref "J15") (pin "e35") (pinfunction "e35_e35") (pintype "bidirectional"))
      (node (ref "J15") (pin "e38") (pinfunction "e38_e38") (pintype "bidirectional"))
      (node (ref "J15") (pin "e4") (pinfunction "e4_e4") (pintype "bidirectional"))
      (node (ref "J15") (pin "e40") (pinfunction "e40_e40") (pintype "bidirectional"))
      (node (ref "J15") (pin "e5") (pinfunction "e5_e5") (pintype "bidirectional"))
      (node (ref "J15") (pin "e8") (pinfunction "e8_e8") (pintype "bidirectional"))
      (node (ref "J15") (pin "f12") (pinfunction "f12_f12") (pintype "bidirectional"))
      (node (ref "J15") (pin "f15") (pinfunction "f15_f15") (pintype "bidirectional"))
      (node (ref "J15") (pin "f18") (pinfunction "f18_f18") (pintype "bidirectional"))
      (node (ref "J15") (pin "f2") (pinfunction "f2_f2") (pintype "bidirectional"))
      (node (ref "J15") (pin "f21") (pinfunction "f21_f21") (pintype "bidirectional"))
      (node (ref "J15") (pin "f24") (pinfunction "f24_f24") (pintype "bidirectional"))
      (node (ref "J15") (pin "f27") (pinfunction "f27_f27") (pintype "bidirectional"))
      (node (ref "J15") (pin "f3") (pinfunction "f3_f3") (pintype "bidirectional"))
      (node (ref "J15") (pin "f30") (pinfunction "f30_f30") (pintype "bidirectional"))
      (node (ref "J15") (pin "f33") (pinfunction "f33_f33") (pintype "bidirectional"))
      (node (ref "J15") (pin "f36") (pinfunction "f36_f36") (pintype "bidirectional"))
      (node (ref "J15") (pin "f39") (pinfunction "f39_f39") (pintype "bidirectional"))
      (node (ref "J15") (pin "f6") (pinfunction "f6_f6") (pintype "bidirectional"))
      (node (ref "J15") (pin "f9") (pinfunction "f9_f9") (pintype "bidirectional"))
      (node (ref "J15") (pin "g1") (pinfunction "g1_g1") (pintype "bidirectional"))
      (node (ref "J15") (pin "g11") (pinfunction "g11_g11") (pintype "bidirectional"))
      (node (ref "J15") (pin "g14") (pinfunction "g14_g14") (pintype "bidirectional"))
      (node (ref "J15") (pin "g17") (pinfunction "g17_g17") (pintype "bidirectional"))
      (node (ref "J15") (pin "g20") (pinfunction "g20_g20") (pintype "bidirectional"))
      (node (ref "J15") (pin "g23") (pinfunction "g23_g23") (pintype "bidirectional"))
      (node (ref "J15") (pin "g26") (pinfunction "g26_g26") (pintype "bidirectional"))
      (node (ref "J15") (pin "g29") (pinfunction "g29_g29") (pintype "bidirectional"))
      (node (ref "J15") (pin "g32") (pinfunction "g32_g32") (pintype "bidirectional"))
      (node (ref "J15") (pin "g35") (pinfunction "g35_g35") (pintype "bidirectional"))
      (node (ref "J15") (pin "g38") (pinfunction "g38_g38") (pintype "bidirectional"))
      (node (ref "J15") (pin "g4") (pinfunction "g4_g4") (pintype "bidirectional"))
      (node (ref "J15") (pin "g40") (pinfunction "g40_g40") (pintype "bidirectional"))
      (node (ref "J15") (pin "g5") (pinfunction "g5_g5") (pintype "bidirectional"))
      (node (ref "J15") (pin "g8") (pinfunction "g8_g8") (pintype "bidirectional"))
      (node (ref "J15") (pin "h12") (pinfunction "h12_h12") (pintype "bidirectional"))
      (node (ref "J15") (pin "h15") (pinfunction "h15_h15") (pintype "bidirectional"))
      (node (ref "J15") (pin "h18") (pinfunction "h18_h18") (pintype "bidirectional"))
      (node (ref "J15") (pin "h21") (pinfunction "h21_h21") (pintype "bidirectional"))
      (node (ref "J15") (pin "h24") (pinfunction "h24_h24") (pintype "bidirectional"))
      (node (ref "J15") (pin "h27") (pinfunction "h27_h27") (pintype "bidirectional"))
      (node (ref "J15") (pin "h3") (pinfunction "h3_h3") (pintype "bidirectional"))
      (node (ref "J15") (pin "h30") (pinfunction "h30_h30") (pintype "bidirectional"))
      (node (ref "J15") (pin "h33") (pinfunction "h33_h33") (pintype "bidirectional"))
      (node (ref "J15") (pin "h36") (pinfunction "h36_h36") (pintype "bidirectional"))
      (node (ref "J15") (pin "h39") (pinfunction "h39_h39") (pintype "bidirectional"))
      (node (ref "J15") (pin "h6") (pinfunction "h6_h6") (pintype "bidirectional"))
      (node (ref "J15") (pin "h9") (pinfunction "h9_h9") (pintype "bidirectional"))
      (node (ref "J15") (pin "j1") (pinfunction "j1_j1") (pintype "bidirectional"))
      (node (ref "J15") (pin "j11") (pinfunction "j11_j11") (pintype "bidirectional"))
      (node (ref "J15") (pin "j14") (pinfunction "j14_j14") (pintype "bidirectional"))
      (node (ref "J15") (pin "j17") (pinfunction "j17_j17") (pintype "bidirectional"))
      (node (ref "J15") (pin "j20") (pinfunction "j20_j20") (pintype "bidirectional"))
      (node (ref "J15") (pin "j23") (pinfunction "j23_j23") (pintype "bidirectional"))
      (node (ref "J15") (pin "j26") (pinfunction "j26_j26") (pintype "bidirectional"))
      (node (ref "J15") (pin "j29") (pinfunction "j29_j29") (pintype "bidirectional"))
      (node (ref "J15") (pin "j32") (pinfunction "j32_j32") (pintype "bidirectional"))
      (node (ref "J15") (pin "j35") (pinfunction "j35_j35") (pintype "bidirectional"))
      (node (ref "J15") (pin "j38") (pinfunction "j38_j38") (pintype "bidirectional"))
      (node (ref "J15") (pin "j4") (pinfunction "j4_j4") (pintype "bidirectional"))
      (node (ref "J15") (pin "j40") (pinfunction "j40_j40") (pintype "bidirectional"))
      (node (ref "J15") (pin "j5") (pinfunction "j5_j5") (pintype "bidirectional"))
      (node (ref "J15") (pin "j8") (pinfunction "j8_j8") (pintype "bidirectional"))
      (node (ref "J15") (pin "k12") (pinfunction "k12_k12") (pintype "bidirectional"))
      (node (ref "J15") (pin "k15") (pinfunction "k15_k15") (pintype "bidirectional"))
      (node (ref "J15") (pin "k18") (pinfunction "k18_k18") (pintype "bidirectional"))
      (node (ref "J15") (pin "k2") (pinfunction "k2_k2") (pintype "bidirectional"))
      (node (ref "J15") (pin "k21") (pinfunction "k21_k21") (pintype "bidirectional"))
      (node (ref "J15") (pin "k24") (pinfunction "k24_k24") (pintype "bidirectional"))
      (node (ref "J15") (pin "k27") (pinfunction "k27_k27") (pintype "bidirectional"))
      (node (ref "J15") (pin "k3") (pinfunction "k3_k3") (pintype "bidirectional"))
      (node (ref "J15") (pin "k30") (pinfunction "k30_k30") (pintype "bidirectional"))
      (node (ref "J15") (pin "k33") (pinfunction "k33_k33") (pintype "bidirectional"))
      (node (ref "J15") (pin "k36") (pinfunction "k36_k36") (pintype "bidirectional"))
      (node (ref "J15") (pin "k39") (pinfunction "k39_k39") (pintype "bidirectional"))
      (node (ref "J15") (pin "k6") (pinfunction "k6_k6") (pintype "bidirectional"))
      (node (ref "J15") (pin "k9") (pinfunction "k9_k9") (pintype "bidirectional"))
    )
    (net (code "232") (name "unconnected-(J15-Pada14)") (class "Default")
      (node (ref "J15") (pin "a14") (pinfunction "a14_a14") (pintype "bidirectional"))
    )
    (net (code "233") (name "unconnected-(J15-Pada15)") (class "Default")
      (node (ref "J15") (pin "a15") (pinfunction "a15_a15") (pintype "bidirectional"))
    )
    (net (code "234") (name "unconnected-(J15-Pada18)") (class "Default")
      (node (ref "J15") (pin "a18") (pinfunction "a18_a18") (pintype "bidirectional"))
    )
    (net (code "235") (name "unconnected-(J15-Pada19)") (class "Default")
      (node (ref "J15") (pin "a19") (pinfunction "a19_a19") (pintype "bidirectional"))
    )
    (net (code "236") (name "unconnected-(J15-Pada34)") (class "Default")
      (node (ref "J15") (pin "a34") (pinfunction "a34_a34") (pintype "bidirectional"))
    )
    (net (code "237") (name "unconnected-(J15-Pada35)") (class "Default")
      (node (ref "J15") (pin "a35") (pinfunction "a35_a35") (pintype "bidirectional"))
    )
    (net (code "238") (name "unconnected-(J15-Pada38)") (class "Default")
      (node (ref "J15") (pin "a38") (pinfunction "a38_a38") (pintype "bidirectional"))
    )
    (net (code "239") (name "unconnected-(J15-Pada39)") (class "Default")
      (node (ref "J15") (pin "a39") (pinfunction "a39_a39") (pintype "bidirectional"))
    )
    (net (code "240") (name "unconnected-(J15-Padb4)") (class "Default")
      (node (ref "J15") (pin "b4") (pinfunction "b4_b4") (pintype "bidirectional"))
    )
    (net (code "241") (name "unconnected-(J15-Padb5)") (class "Default")
      (node (ref "J15") (pin "b5") (pinfunction "b5_b5") (pintype "bidirectional"))
    )
    (net (code "242") (name "unconnected-(J15-Padb8)") (class "Default")
      (node (ref "J15") (pin "b8") (pinfunction "b8_b8") (pintype "bidirectional"))
    )
    (net (code "243") (name "unconnected-(J15-Padb9)") (class "Default")
      (node (ref "J15") (pin "b9") (pinfunction "b9_b9") (pintype "bidirectional"))
    )
    (net (code "244") (name "unconnected-(J15-Padb12)") (class "Default")
      (node (ref "J15") (pin "b12") (pinfunction "b12_b12") (pintype "bidirectional"))
    )
    (net (code "245") (name "unconnected-(J15-Padb13)") (class "Default")
      (node (ref "J15") (pin "b13") (pinfunction "b13_b13") (pintype "bidirectional"))
    )
    (net (code "246") (name "unconnected-(J15-Padb16)") (class "Default")
      (node (ref "J15") (pin "b16") (pinfunction "b16_b16") (pintype "bidirectional"))
    )
    (net (code "247") (name "unconnected-(J15-Padb17)") (class "Default")
      (node (ref "J15") (pin "b17") (pinfunction "b17_b17") (pintype "bidirectional"))
    )
    (net (code "248") (name "unconnected-(J15-Padb24)") (class "Default")
      (node (ref "J15") (pin "b24") (pinfunction "b24_b24") (pintype "bidirectional"))
    )
    (net (code "249") (name "unconnected-(J15-Padb25)") (class "Default")
      (node (ref "J15") (pin "b25") (pinfunction "b25_b25") (pintype "bidirectional"))
    )
    (net (code "250") (name "unconnected-(J15-Padb28)") (class "Default")
      (node (ref "J15") (pin "b28") (pinfunction "b28_b28") (pintype "bidirectional"))
    )
    (net (code "251") (name "unconnected-(J15-Padb29)") (class "Default")
      (node (ref "J15") (pin "b29") (pinfunction "b29_b29") (pintype "bidirectional"))
    )
    (net (code "252") (name "unconnected-(J15-Padb32)") (class "Default")
      (node (ref "J15") (pin "b32") (pinfunction "b32_b32") (pintype "bidirectional"))
    )
    (net (code "253") (name "unconnected-(J15-Padb33)") (class "Default")
      (node (ref "J15") (pin "b33") (pinfunction "b33_b33") (pintype "bidirectional"))
    )
    (net (code "254") (name "unconnected-(J15-Padb36)") (class "Default")
      (node (ref "J15") (pin "b36") (pinfunction "b36_b36") (pintype "bidirectional"))
    )
    (net (code "255") (name "unconnected-(J15-Padb37)") (class "Default")
      (node (ref "J15") (pin "b37") (pinfunction "b37_b37") (pintype "bidirectional"))
    )
    (net (code "256") (name "unconnected-(J15-Padb40)") (class "Default")
      (node (ref "J15") (pin "b40") (pinfunction "b40_b40") (pintype "bidirectional"))
    )
    (net (code "257") (name "unconnected-(J15-Padj39)") (class "Default")
      (node (ref "J15") (pin "j39") (pinfunction "j39_j39") (pintype "bidirectional"))
    )
    (net (code "258") (name "unconnected-(J15-Padk40)") (class "Default")
      (node (ref "J15") (pin "k40") (pinfunction "k40_k40") (pintype "bidirectional"))
    )
  )
)
